# Connector_Sheet.net
KiCad netlist of a schematic drawn in Altium Designer
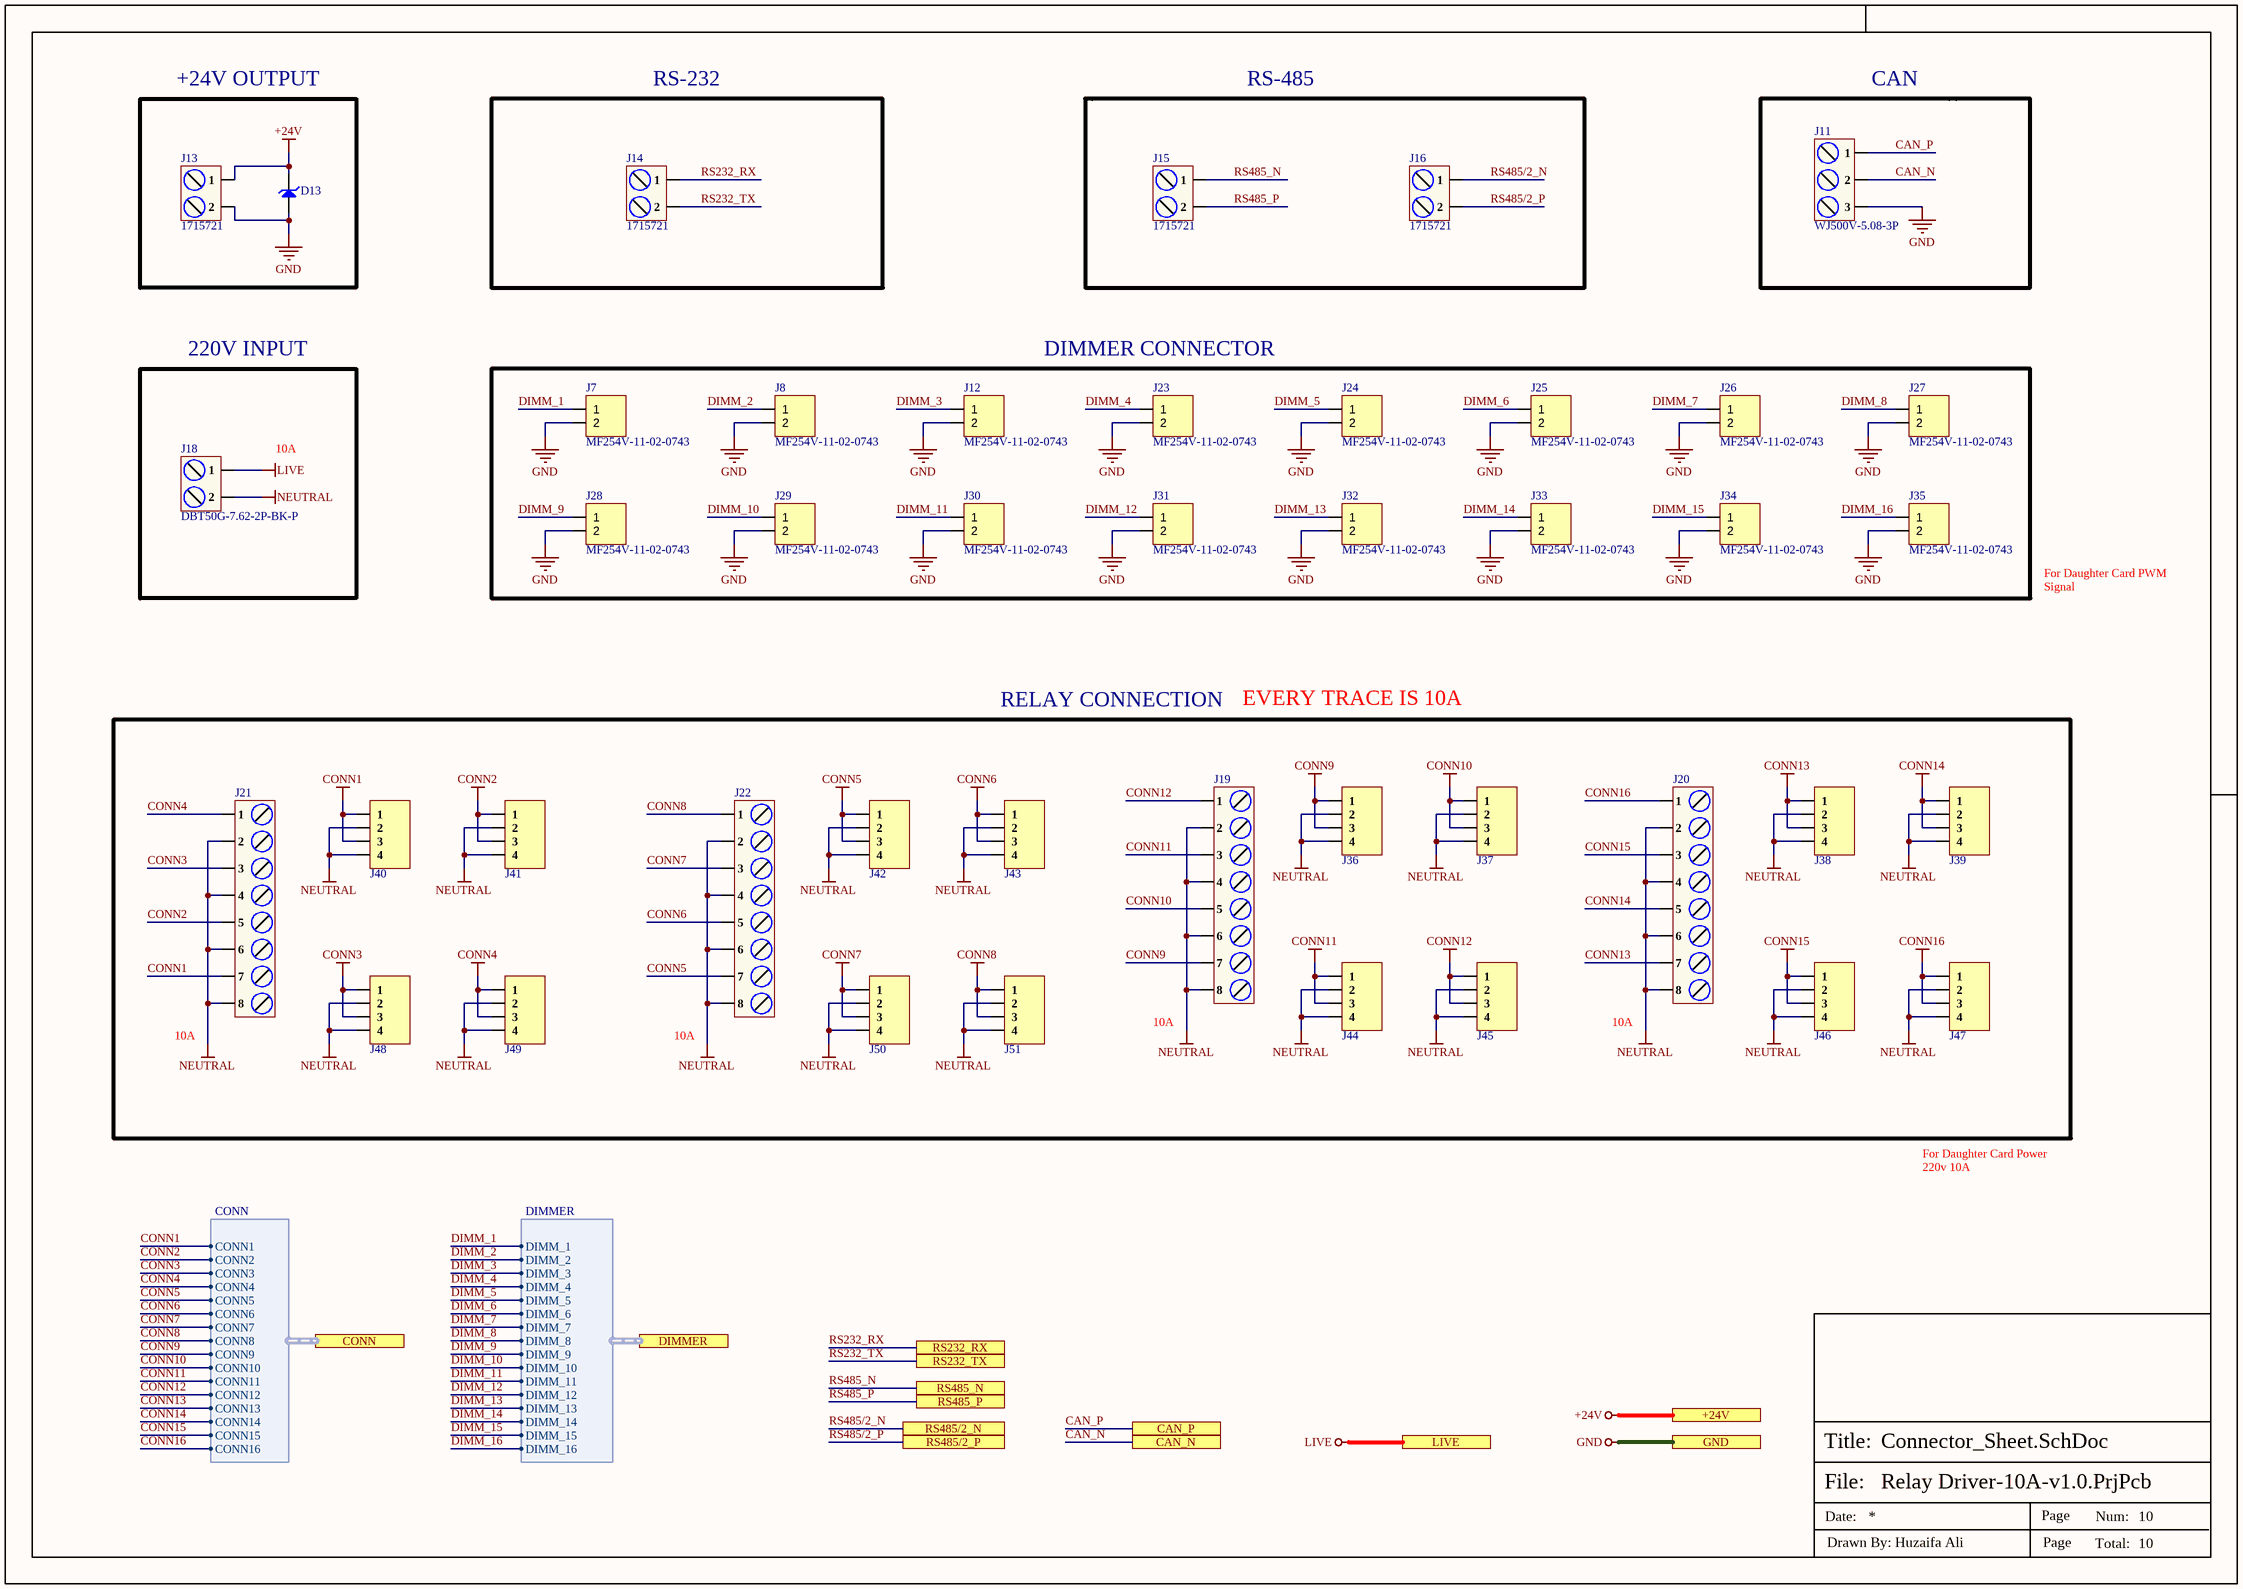
[diagram p0: Connector_Sheet.SchDoc]

(export (version "E")
  (design (tool "Eeschema 10.0.6"))
  (components
    (comp (ref "D13")
      (value "SMBJ28A-13-F")
      (footprint "SMB_")
      (description "TVS DIODE 28VWM 45.4VC SMB")
      (fields (field (name "MANUFACTURER") "Diodes"))
      (libsource (lib "eSpark Libraries") (part "SMBJ28A-13-F"))
    )
    (comp (ref "J7")
      (value "MF254V-11-02-0743")
      (footprint "MF254V-11-02-0743")
      (fields (field (name "MANUFACTURER") "XFCN") (field (name "LCSC PART NUMBER") "C2889984"))
      (libsource (lib "SchLib") (part "MF254V-11-02-0743"))
    )
    (comp (ref "J8")
      (value "MF254V-11-02-0743")
      (footprint "MF254V-11-02-0743")
      (fields (field (name "MANUFACTURER") "XFCN") (field (name "LCSC PART NUMBER") "C2889984"))
      (libsource (lib "SchLib") (part "MF254V-11-02-0743"))
    )
    (comp (ref "J11")
      (value "WJ500V-5.08-3P")
      (footprint "WJ500V-5.08-3P")
      (fields (field (name "MANUFACTURER") "Ningbo Kangnex Elec") (field (name "LCSC PART NUMBER") "C72334"))
      (libsource (lib "eSpark Libraries") (part "WJ500V-5.08-3P"))
    )
    (comp (ref "J12")
      (value "MF254V-11-02-0743")
      (footprint "MF254V-11-02-0743")
      (fields (field (name "MANUFACTURER") "XFCN") (field (name "LCSC PART NUMBER") "C2889984"))
      (libsource (lib "SchLib") (part "MF254V-11-02-0743"))
    )
    (comp (ref "J13")
      (value "1715721")
      (footprint "1715721")
      (description "TERM BLK 2P SIDE ENT 5.08MM PCB")
      (fields (field (name "MANUFACTURER") "Phoenix Contact"))
      (libsource (lib "eSpark Libraries") (part "1715721"))
    )
    (comp (ref "J14")
      (value "1715721")
      (footprint "1715721")
      (description "TERM BLK 2P SIDE ENT 5.08MM PCB")
      (fields (field (name "MANUFACTURER") "Phoenix Contact"))
      (libsource (lib "eSpark Libraries") (part "1715721"))
    )
    (comp (ref "J15")
      (value "1715721")
      (footprint "1715721")
      (description "TERM BLK 2P SIDE ENT 5.08MM PCB")
      (fields (field (name "MANUFACTURER") "Phoenix Contact"))
      (libsource (lib "eSpark Libraries") (part "1715721"))
    )
    (comp (ref "J16")
      (value "1715721")
      (footprint "1715721")
      (description "TERM BLK 2P SIDE ENT 5.08MM PCB")
      (fields (field (name "MANUFACTURER") "Phoenix Contact"))
      (libsource (lib "eSpark Libraries") (part "1715721"))
    )
    (comp (ref "J18")
      (value "DBT50G-7.62-2P-BK-P")
      (footprint "DBT50G-7.62-2P-BK-P")
      (fields (field (name "MANUFACTURER") "DORABO") (field (name "LCSC PART NUMBER") "C496127"))
      (libsource (lib "eSpark Libraries") (part "DBT50G-7.62-2P-BK-P"))
    )
    (comp (ref "J19")
      (value "DBT50G-7.62-8P-BK-P")
      (footprint "DBT50G-7.62-8P-BK-P")
      (fields (field (name "MANUFACTURER") "DORABO") (field (name "LCSC PART NUMBER") "C918112"))
      (libsource (lib "eSpark Libraries") (part "DBT50G-7.62-8P-BK-P"))
    )
    (comp (ref "J20")
      (value "DBT50G-7.62-8P-BK-P")
      (footprint "DBT50G-7.62-8P-BK-P")
      (fields (field (name "MANUFACTURER") "DORABO") (field (name "LCSC PART NUMBER") "C918112"))
      (libsource (lib "eSpark Libraries") (part "DBT50G-7.62-8P-BK-P"))
    )
    (comp (ref "J21")
      (value "DBT50G-7.62-8P-BK-P")
      (footprint "DBT50G-7.62-8P-BK-P")
      (fields (field (name "MANUFACTURER") "DORABO") (field (name "LCSC PART NUMBER") "C918112"))
      (libsource (lib "eSpark Libraries") (part "DBT50G-7.62-8P-BK-P"))
    )
    (comp (ref "J22")
      (value "DBT50G-7.62-8P-BK-P")
      (footprint "DBT50G-7.62-8P-BK-P")
      (fields (field (name "MANUFACTURER") "DORABO") (field (name "LCSC PART NUMBER") "C918112"))
      (libsource (lib "eSpark Libraries") (part "DBT50G-7.62-8P-BK-P"))
    )
    (comp (ref "J23")
      (value "MF254V-11-02-0743")
      (footprint "MF254V-11-02-0743")
      (fields (field (name "MANUFACTURER") "XFCN") (field (name "LCSC PART NUMBER") "C2889984"))
      (libsource (lib "SchLib") (part "MF254V-11-02-0743"))
    )
    (comp (ref "J24")
      (value "MF254V-11-02-0743")
      (footprint "MF254V-11-02-0743")
      (fields (field (name "MANUFACTURER") "XFCN") (field (name "LCSC PART NUMBER") "C2889984"))
      (libsource (lib "SchLib") (part "MF254V-11-02-0743"))
    )
    (comp (ref "J25")
      (value "MF254V-11-02-0743")
      (footprint "MF254V-11-02-0743")
      (fields (field (name "MANUFACTURER") "XFCN") (field (name "LCSC PART NUMBER") "C2889984"))
      (libsource (lib "SchLib") (part "MF254V-11-02-0743"))
    )
    (comp (ref "J26")
      (value "MF254V-11-02-0743")
      (footprint "MF254V-11-02-0743")
      (fields (field (name "MANUFACTURER") "XFCN") (field (name "LCSC PART NUMBER") "C2889984"))
      (libsource (lib "SchLib") (part "MF254V-11-02-0743"))
    )
    (comp (ref "J27")
      (value "MF254V-11-02-0743")
      (footprint "MF254V-11-02-0743")
      (fields (field (name "MANUFACTURER") "XFCN") (field (name "LCSC PART NUMBER") "C2889984"))
      (libsource (lib "SchLib") (part "MF254V-11-02-0743"))
    )
    (comp (ref "J28")
      (value "MF254V-11-02-0743")
      (footprint "MF254V-11-02-0743")
      (fields (field (name "MANUFACTURER") "XFCN") (field (name "LCSC PART NUMBER") "C2889984"))
      (libsource (lib "SchLib") (part "MF254V-11-02-0743"))
    )
    (comp (ref "J29")
      (value "MF254V-11-02-0743")
      (footprint "MF254V-11-02-0743")
      (fields (field (name "MANUFACTURER") "XFCN") (field (name "LCSC PART NUMBER") "C2889984"))
      (libsource (lib "SchLib") (part "MF254V-11-02-0743"))
    )
    (comp (ref "J30")
      (value "MF254V-11-02-0743")
      (footprint "MF254V-11-02-0743")
      (fields (field (name "MANUFACTURER") "XFCN") (field (name "LCSC PART NUMBER") "C2889984"))
      (libsource (lib "SchLib") (part "MF254V-11-02-0743"))
    )
    (comp (ref "J31")
      (value "MF254V-11-02-0743")
      (footprint "MF254V-11-02-0743")
      (fields (field (name "MANUFACTURER") "XFCN") (field (name "LCSC PART NUMBER") "C2889984"))
      (libsource (lib "SchLib") (part "MF254V-11-02-0743"))
    )
    (comp (ref "J32")
      (value "MF254V-11-02-0743")
      (footprint "MF254V-11-02-0743")
      (fields (field (name "MANUFACTURER") "XFCN") (field (name "LCSC PART NUMBER") "C2889984"))
      (libsource (lib "SchLib") (part "MF254V-11-02-0743"))
    )
    (comp (ref "J33")
      (value "MF254V-11-02-0743")
      (footprint "MF254V-11-02-0743")
      (fields (field (name "MANUFACTURER") "XFCN") (field (name "LCSC PART NUMBER") "C2889984"))
      (libsource (lib "SchLib") (part "MF254V-11-02-0743"))
    )
    (comp (ref "J34")
      (value "MF254V-11-02-0743")
      (footprint "MF254V-11-02-0743")
      (fields (field (name "MANUFACTURER") "XFCN") (field (name "LCSC PART NUMBER") "C2889984"))
      (libsource (lib "SchLib") (part "MF254V-11-02-0743"))
    )
    (comp (ref "J35")
      (value "MF254V-11-02-0743")
      (footprint "MF254V-11-02-0743")
      (fields (field (name "MANUFACTURER") "XFCN") (field (name "LCSC PART NUMBER") "C2889984"))
      (libsource (lib "SchLib") (part "MF254V-11-02-0743"))
    )
    (comp (ref "J36")
      (value "0447690401")
      (description "4 Position Receptacle Connector 0.118\" (3.00mm) Through Hole Tin")
      (fields (field (name "MANUFACTURER") "Molex") (field (name "DIGIKEY PART NUMBER") "23-0447690401-ND"))
      (libsource (lib "SchLib") (part "0447690401"))
    )
    (comp (ref "J37")
      (value "0447690401")
      (description "4 Position Receptacle Connector 0.118\" (3.00mm) Through Hole Tin")
      (fields (field (name "MANUFACTURER") "Molex") (field (name "DIGIKEY PART NUMBER") "23-0447690401-ND"))
      (libsource (lib "SchLib") (part "0447690401"))
    )
    (comp (ref "J38")
      (value "0447690401")
      (description "4 Position Receptacle Connector 0.118\" (3.00mm) Through Hole Tin")
      (fields (field (name "MANUFACTURER") "Molex") (field (name "DIGIKEY PART NUMBER") "23-0447690401-ND"))
      (libsource (lib "SchLib") (part "0447690401"))
    )
    (comp (ref "J39")
      (value "0447690401")
      (description "4 Position Receptacle Connector 0.118\" (3.00mm) Through Hole Tin")
      (fields (field (name "MANUFACTURER") "Molex") (field (name "DIGIKEY PART NUMBER") "23-0447690401-ND"))
      (libsource (lib "SchLib") (part "0447690401"))
    )
    (comp (ref "J40")
      (value "0447690401")
      (description "4 Position Receptacle Connector 0.118\" (3.00mm) Through Hole Tin")
      (fields (field (name "MANUFACTURER") "Molex") (field (name "DIGIKEY PART NUMBER") "23-0447690401-ND"))
      (libsource (lib "SchLib") (part "0447690401"))
    )
    (comp (ref "J41")
      (value "0447690401")
      (description "4 Position Receptacle Connector 0.118\" (3.00mm) Through Hole Tin")
      (fields (field (name "MANUFACTURER") "Molex") (field (name "DIGIKEY PART NUMBER") "23-0447690401-ND"))
      (libsource (lib "SchLib") (part "0447690401"))
    )
    (comp (ref "J42")
      (value "0447690401")
      (description "4 Position Receptacle Connector 0.118\" (3.00mm) Through Hole Tin")
      (fields (field (name "MANUFACTURER") "Molex") (field (name "DIGIKEY PART NUMBER") "23-0447690401-ND"))
      (libsource (lib "SchLib") (part "0447690401"))
    )
    (comp (ref "J43")
      (value "0447690401")
      (description "4 Position Receptacle Connector 0.118\" (3.00mm) Through Hole Tin")
      (fields (field (name "MANUFACTURER") "Molex") (field (name "DIGIKEY PART NUMBER") "23-0447690401-ND"))
      (libsource (lib "SchLib") (part "0447690401"))
    )
    (comp (ref "J44")
      (value "0447690401")
      (description "4 Position Receptacle Connector 0.118\" (3.00mm) Through Hole Tin")
      (fields (field (name "MANUFACTURER") "Molex") (field (name "DIGIKEY PART NUMBER") "23-0447690401-ND"))
      (libsource (lib "SchLib") (part "0447690401"))
    )
    (comp (ref "J45")
      (value "0447690401")
      (description "4 Position Receptacle Connector 0.118\" (3.00mm) Through Hole Tin")
      (fields (field (name "MANUFACTURER") "Molex") (field (name "DIGIKEY PART NUMBER") "23-0447690401-ND"))
      (libsource (lib "SchLib") (part "0447690401"))
    )
    (comp (ref "J46")
      (value "0447690401")
      (description "4 Position Receptacle Connector 0.118\" (3.00mm) Through Hole Tin")
      (fields (field (name "MANUFACTURER") "Molex") (field (name "DIGIKEY PART NUMBER") "23-0447690401-ND"))
      (libsource (lib "SchLib") (part "0447690401"))
    )
    (comp (ref "J47")
      (value "0447690401")
      (description "4 Position Receptacle Connector 0.118\" (3.00mm) Through Hole Tin")
      (fields (field (name "MANUFACTURER") "Molex") (field (name "DIGIKEY PART NUMBER") "23-0447690401-ND"))
      (libsource (lib "SchLib") (part "0447690401"))
    )
    (comp (ref "J48")
      (value "0447690401")
      (description "4 Position Receptacle Connector 0.118\" (3.00mm) Through Hole Tin")
      (fields (field (name "MANUFACTURER") "Molex") (field (name "DIGIKEY PART NUMBER") "23-0447690401-ND"))
      (libsource (lib "SchLib") (part "0447690401"))
    )
    (comp (ref "J49")
      (value "0447690401")
      (description "4 Position Receptacle Connector 0.118\" (3.00mm) Through Hole Tin")
      (fields (field (name "MANUFACTURER") "Molex") (field (name "DIGIKEY PART NUMBER") "23-0447690401-ND"))
      (libsource (lib "SchLib") (part "0447690401"))
    )
    (comp (ref "J50")
      (value "0447690401")
      (description "4 Position Receptacle Connector 0.118\" (3.00mm) Through Hole Tin")
      (fields (field (name "MANUFACTURER") "Molex") (field (name "DIGIKEY PART NUMBER") "23-0447690401-ND"))
      (libsource (lib "SchLib") (part "0447690401"))
    )
    (comp (ref "J51")
      (value "0447690401")
      (description "4 Position Receptacle Connector 0.118\" (3.00mm) Through Hole Tin")
      (fields (field (name "MANUFACTURER") "Molex") (field (name "DIGIKEY PART NUMBER") "23-0447690401-ND"))
      (libsource (lib "SchLib") (part "0447690401"))
    )
  )
  (nets
    (net (code "3") (name "+24V") (class "Default")
      (node (ref "D13") (pin "2") (pinfunction "K_2") (pintype "passive"))
      (node (ref "J13") (pin "1") (pinfunction "1_1") (pintype "passive"))
    )
    (net (code "4") (name "/CAN_N") (class "Default")
      (node (ref "J11") (pin "2") (pinfunction "2_2") (pintype "passive"))
    )
    (net (code "5") (name "/CAN_P") (class "Default")
      (node (ref "J11") (pin "1") (pinfunction "1_1") (pintype "passive"))
    )
    (net (code "6") (name "/DIMM_1") (class "Default")
      (node (ref "J7") (pin "1") (pinfunction "1_1") (pintype "passive"))
    )
    (net (code "7") (name "/DIMM_2") (class "Default")
      (node (ref "J8") (pin "1") (pinfunction "1_1") (pintype "passive"))
    )
    (net (code "8") (name "/DIMM_3") (class "Default")
      (node (ref "J12") (pin "1") (pinfunction "1_1") (pintype "passive"))
    )
    (net (code "9") (name "/DIMM_4") (class "Default")
      (node (ref "J23") (pin "1") (pinfunction "1_1") (pintype "passive"))
    )
    (net (code "10") (name "/DIMM_5") (class "Default")
      (node (ref "J24") (pin "1") (pinfunction "1_1") (pintype "passive"))
    )
    (net (code "11") (name "/DIMM_6") (class "Default")
      (node (ref "J25") (pin "1") (pinfunction "1_1") (pintype "passive"))
    )
    (net (code "12") (name "/DIMM_7") (class "Default")
      (node (ref "J26") (pin "1") (pinfunction "1_1") (pintype "passive"))
    )
    (net (code "13") (name "/DIMM_8") (class "Default")
      (node (ref "J27") (pin "1") (pinfunction "1_1") (pintype "passive"))
    )
    (net (code "14") (name "/DIMM_9") (class "Default")
      (node (ref "J28") (pin "1") (pinfunction "1_1") (pintype "passive"))
    )
    (net (code "15") (name "/DIMM_10") (class "Default")
      (node (ref "J29") (pin "1") (pinfunction "1_1") (pintype "passive"))
    )
    (net (code "16") (name "/DIMM_11") (class "Default")
      (node (ref "J30") (pin "1") (pinfunction "1_1") (pintype "passive"))
    )
    (net (code "17") (name "/DIMM_12") (class "Default")
      (node (ref "J31") (pin "1") (pinfunction "1_1") (pintype "passive"))
    )
    (net (code "18") (name "/DIMM_13") (class "Default")
      (node (ref "J32") (pin "1") (pinfunction "1_1") (pintype "passive"))
    )
    (net (code "19") (name "/DIMM_14") (class "Default")
      (node (ref "J33") (pin "1") (pinfunction "1_1") (pintype "passive"))
    )
    (net (code "20") (name "/DIMM_15") (class "Default")
      (node (ref "J34") (pin "1") (pinfunction "1_1") (pintype "passive"))
    )
    (net (code "21") (name "/DIMM_16") (class "Default")
      (node (ref "J35") (pin "1") (pinfunction "1_1") (pintype "passive"))
    )
    (net (code "22") (name "/RS232_RX") (class "Default")
      (node (ref "J14") (pin "1") (pinfunction "1_1") (pintype "passive"))
    )
    (net (code "23") (name "/RS232_TX") (class "Default")
      (node (ref "J14") (pin "2") (pinfunction "2_2") (pintype "passive"))
    )
    (net (code "24") (name "/RS485_N") (class "Default")
      (node (ref "J15") (pin "1") (pinfunction "1_1") (pintype "passive"))
    )
    (net (code "25") (name "/RS485_P") (class "Default")
      (node (ref "J15") (pin "2") (pinfunction "2_2") (pintype "passive"))
    )
    (net (code "26") (name "/RS485{slash}2_N") (class "Default")
      (node (ref "J16") (pin "1") (pinfunction "1_1") (pintype "passive"))
    )
    (net (code "27") (name "/RS485{slash}2_P") (class "Default")
      (node (ref "J16") (pin "2") (pinfunction "2_2") (pintype "passive"))
    )
    (net (code "30") (name "CONN1") (class "Default")
      (node (ref "J21") (pin "7") (pinfunction "7_7") (pintype "passive"))
      (node (ref "J40") (pin "1") (pinfunction "1_1") (pintype "passive"))
      (node (ref "J40") (pin "3") (pinfunction "3_3") (pintype "passive"))
    )
    (net (code "31") (name "CONN2") (class "Default")
      (node (ref "J21") (pin "5") (pinfunction "5_5") (pintype "passive"))
      (node (ref "J41") (pin "1") (pinfunction "1_1") (pintype "passive"))
      (node (ref "J41") (pin "3") (pinfunction "3_3") (pintype "passive"))
    )
    (net (code "32") (name "CONN3") (class "Default")
      (node (ref "J21") (pin "3") (pinfunction "3_3") (pintype "passive"))
      (node (ref "J48") (pin "1") (pinfunction "1_1") (pintype "passive"))
      (node (ref "J48") (pin "3") (pinfunction "3_3") (pintype "passive"))
    )
    (net (code "33") (name "CONN4") (class "Default")
      (node (ref "J21") (pin "1") (pinfunction "1_1") (pintype "passive"))
      (node (ref "J49") (pin "1") (pinfunction "1_1") (pintype "passive"))
      (node (ref "J49") (pin "3") (pinfunction "3_3") (pintype "passive"))
    )
    (net (code "34") (name "CONN5") (class "Default")
      (node (ref "J22") (pin "7") (pinfunction "7_7") (pintype "passive"))
      (node (ref "J42") (pin "1") (pinfunction "1_1") (pintype "passive"))
      (node (ref "J42") (pin "3") (pinfunction "3_3") (pintype "passive"))
    )
    (net (code "35") (name "CONN6") (class "Default")
      (node (ref "J22") (pin "5") (pinfunction "5_5") (pintype "passive"))
      (node (ref "J43") (pin "1") (pinfunction "1_1") (pintype "passive"))
      (node (ref "J43") (pin "3") (pinfunction "3_3") (pintype "passive"))
    )
    (net (code "36") (name "CONN7") (class "Default")
      (node (ref "J22") (pin "3") (pinfunction "3_3") (pintype "passive"))
      (node (ref "J50") (pin "1") (pinfunction "1_1") (pintype "passive"))
      (node (ref "J50") (pin "3") (pinfunction "3_3") (pintype "passive"))
    )
    (net (code "37") (name "CONN8") (class "Default")
      (node (ref "J22") (pin "1") (pinfunction "1_1") (pintype "passive"))
      (node (ref "J51") (pin "1") (pinfunction "1_1") (pintype "passive"))
      (node (ref "J51") (pin "3") (pinfunction "3_3") (pintype "passive"))
    )
    (net (code "38") (name "CONN9") (class "Default")
      (node (ref "J19") (pin "7") (pinfunction "7_7") (pintype "passive"))
      (node (ref "J36") (pin "1") (pinfunction "1_1") (pintype "passive"))
      (node (ref "J36") (pin "3") (pinfunction "3_3") (pintype "passive"))
    )
    (net (code "39") (name "CONN10") (class "Default")
      (node (ref "J19") (pin "5") (pinfunction "5_5") (pintype "passive"))
      (node (ref "J37") (pin "1") (pinfunction "1_1") (pintype "passive"))
      (node (ref "J37") (pin "3") (pinfunction "3_3") (pintype "passive"))
    )
    (net (code "40") (name "CONN11") (class "Default")
      (node (ref "J19") (pin "3") (pinfunction "3_3") (pintype "passive"))
      (node (ref "J44") (pin "1") (pinfunction "1_1") (pintype "passive"))
      (node (ref "J44") (pin "3") (pinfunction "3_3") (pintype "passive"))
    )
    (net (code "41") (name "CONN12") (class "Default")
      (node (ref "J19") (pin "1") (pinfunction "1_1") (pintype "passive"))
      (node (ref "J45") (pin "1") (pinfunction "1_1") (pintype "passive"))
      (node (ref "J45") (pin "3") (pinfunction "3_3") (pintype "passive"))
    )
    (net (code "42") (name "CONN13") (class "Default")
      (node (ref "J20") (pin "7") (pinfunction "7_7") (pintype "passive"))
      (node (ref "J38") (pin "1") (pinfunction "1_1") (pintype "passive"))
      (node (ref "J38") (pin "3") (pinfunction "3_3") (pintype "passive"))
    )
    (net (code "43") (name "CONN14") (class "Default")
      (node (ref "J20") (pin "5") (pinfunction "5_5") (pintype "passive"))
      (node (ref "J39") (pin "1") (pinfunction "1_1") (pintype "passive"))
      (node (ref "J39") (pin "3") (pinfunction "3_3") (pintype "passive"))
    )
    (net (code "44") (name "CONN15") (class "Default")
      (node (ref "J20") (pin "3") (pinfunction "3_3") (pintype "passive"))
      (node (ref "J46") (pin "1") (pinfunction "1_1") (pintype "passive"))
      (node (ref "J46") (pin "3") (pinfunction "3_3") (pintype "passive"))
    )
    (net (code "45") (name "CONN16") (class "Default")
      (node (ref "J20") (pin "1") (pinfunction "1_1") (pintype "passive"))
      (node (ref "J47") (pin "1") (pinfunction "1_1") (pintype "passive"))
      (node (ref "J47") (pin "3") (pinfunction "3_3") (pintype "passive"))
    )
    (net (code "46") (name "GND") (class "Default")
      (node (ref "D13") (pin "1") (pinfunction "A_1") (pintype "passive"))
      (node (ref "J11") (pin "3") (pinfunction "3_3") (pintype "passive"))
      (node (ref "J12") (pin "2") (pinfunction "2_2") (pintype "passive"))
      (node (ref "J13") (pin "2") (pinfunction "2_2") (pintype "passive"))
      (node (ref "J23") (pin "2") (pinfunction "2_2") (pintype "passive"))
      (node (ref "J24") (pin "2") (pinfunction "2_2") (pintype "passive"))
      (node (ref "J25") (pin "2") (pinfunction "2_2") (pintype "passive"))
      (node (ref "J26") (pin "2") (pinfunction "2_2") (pintype "passive"))
      (node (ref "J27") (pin "2") (pinfunction "2_2") (pintype "passive"))
      (node (ref "J28") (pin "2") (pinfunction "2_2") (pintype "passive"))
      (node (ref "J29") (pin "2") (pinfunction "2_2") (pintype "passive"))
      (node (ref "J30") (pin "2") (pinfunction "2_2") (pintype "passive"))
      (node (ref "J31") (pin "2") (pinfunction "2_2") (pintype "passive"))
      (node (ref "J32") (pin "2") (pinfunction "2_2") (pintype "passive"))
      (node (ref "J33") (pin "2") (pinfunction "2_2") (pintype "passive"))
      (node (ref "J34") (pin "2") (pinfunction "2_2") (pintype "passive"))
      (node (ref "J35") (pin "2") (pinfunction "2_2") (pintype "passive"))
      (node (ref "J7") (pin "2") (pinfunction "2_2") (pintype "passive"))
      (node (ref "J8") (pin "2") (pinfunction "2_2") (pintype "passive"))
    )
    (net (code "47") (name "LIVE") (class "Default")
      (node (ref "J18") (pin "1") (pinfunction "1_1") (pintype "passive"))
    )
    (net (code "48") (name "NEUTRAL") (class "Default")
      (node (ref "J18") (pin "2") (pinfunction "2_2") (pintype "passive"))
      (node (ref "J19") (pin "2") (pinfunction "2_2") (pintype "passive"))
      (node (ref "J19") (pin "4") (pinfunction "4_4") (pintype "passive"))
      (node (ref "J19") (pin "6") (pinfunction "6_6") (pintype "passive"))
      (node (ref "J19") (pin "8") (pinfunction "8_8") (pintype "passive"))
      (node (ref "J20") (pin "2") (pinfunction "2_2") (pintype "passive"))
      (node (ref "J20") (pin "4") (pinfunction "4_4") (pintype "passive"))
      (node (ref "J20") (pin "6") (pinfunction "6_6") (pintype "passive"))
      (node (ref "J20") (pin "8") (pinfunction "8_8") (pintype "passive"))
      (node (ref "J21") (pin "2") (pinfunction "2_2") (pintype "passive"))
      (node (ref "J21") (pin "4") (pinfunction "4_4") (pintype "passive"))
      (node (ref "J21") (pin "6") (pinfunction "6_6") (pintype "passive"))
      (node (ref "J21") (pin "8") (pinfunction "8_8") (pintype "passive"))
      (node (ref "J22") (pin "2") (pinfunction "2_2") (pintype "passive"))
      (node (ref "J22") (pin "4") (pinfunction "4_4") (pintype "passive"))
      (node (ref "J22") (pin "6") (pinfunction "6_6") (pintype "passive"))
      (node (ref "J22") (pin "8") (pinfunction "8_8") (pintype "passive"))
      (node (ref "J36") (pin "2") (pinfunction "2_2") (pintype "passive"))
      (node (ref "J36") (pin "4") (pinfunction "4_4") (pintype "passive"))
      (node (ref "J37") (pin "2") (pinfunction "2_2") (pintype "passive"))
      (node (ref "J37") (pin "4") (pinfunction "4_4") (pintype "passive"))
      (node (ref "J38") (pin "2") (pinfunction "2_2") (pintype "passive"))
      (node (ref "J38") (pin "4") (pinfunction "4_4") (pintype "passive"))
      (node (ref "J39") (pin "2") (pinfunction "2_2") (pintype "passive"))
      (node (ref "J39") (pin "4") (pinfunction "4_4") (pintype "passive"))
      (node (ref "J40") (pin "2") (pinfunction "2_2") (pintype "passive"))
      (node (ref "J40") (pin "4") (pinfunction "4_4") (pintype "passive"))
      (node (ref "J41") (pin "2") (pinfunction "2_2") (pintype "passive"))
      (node (ref "J41") (pin "4") (pinfunction "4_4") (pintype "passive"))
      (node (ref "J42") (pin "2") (pinfunction "2_2") (pintype "passive"))
      (node (ref "J42") (pin "4") (pinfunction "4_4") (pintype "passive"))
      (node (ref "J43") (pin "2") (pinfunction "2_2") (pintype "passive"))
      (node (ref "J43") (pin "4") (pinfunction "4_4") (pintype "passive"))
      (node (ref "J44") (pin "2") (pinfunction "2_2") (pintype "passive"))
      (node (ref "J44") (pin "4") (pinfunction "4_4") (pintype "passive"))
      (node (ref "J45") (pin "2") (pinfunction "2_2") (pintype "passive"))
      (node (ref "J45") (pin "4") (pinfunction "4_4") (pintype "passive"))
      (node (ref "J46") (pin "2") (pinfunction "2_2") (pintype "passive"))
      (node (ref "J46") (pin "4") (pinfunction "4_4") (pintype "passive"))
      (node (ref "J47") (pin "2") (pinfunction "2_2") (pintype "passive"))
      (node (ref "J47") (pin "4") (pinfunction "4_4") (pintype "passive"))
      (node (ref "J48") (pin "2") (pinfunction "2_2") (pintype "passive"))
      (node (ref "J48") (pin "4") (pinfunction "4_4") (pintype "passive"))
      (node (ref "J49") (pin "2") (pinfunction "2_2") (pintype "passive"))
      (node (ref "J49") (pin "4") (pinfunction "4_4") (pintype "passive"))
      (node (ref "J50") (pin "2") (pinfunction "2_2") (pintype "passive"))
      (node (ref "J50") (pin "4") (pinfunction "4_4") (pintype "passive"))
      (node (ref "J51") (pin "2") (pinfunction "2_2") (pintype "passive"))
      (node (ref "J51") (pin "4") (pinfunction "4_4") (pintype "passive"))
    )
  )
)
